# MOD-Y_V02.net
KiCad netlist of a schematic drawn in EAGLE
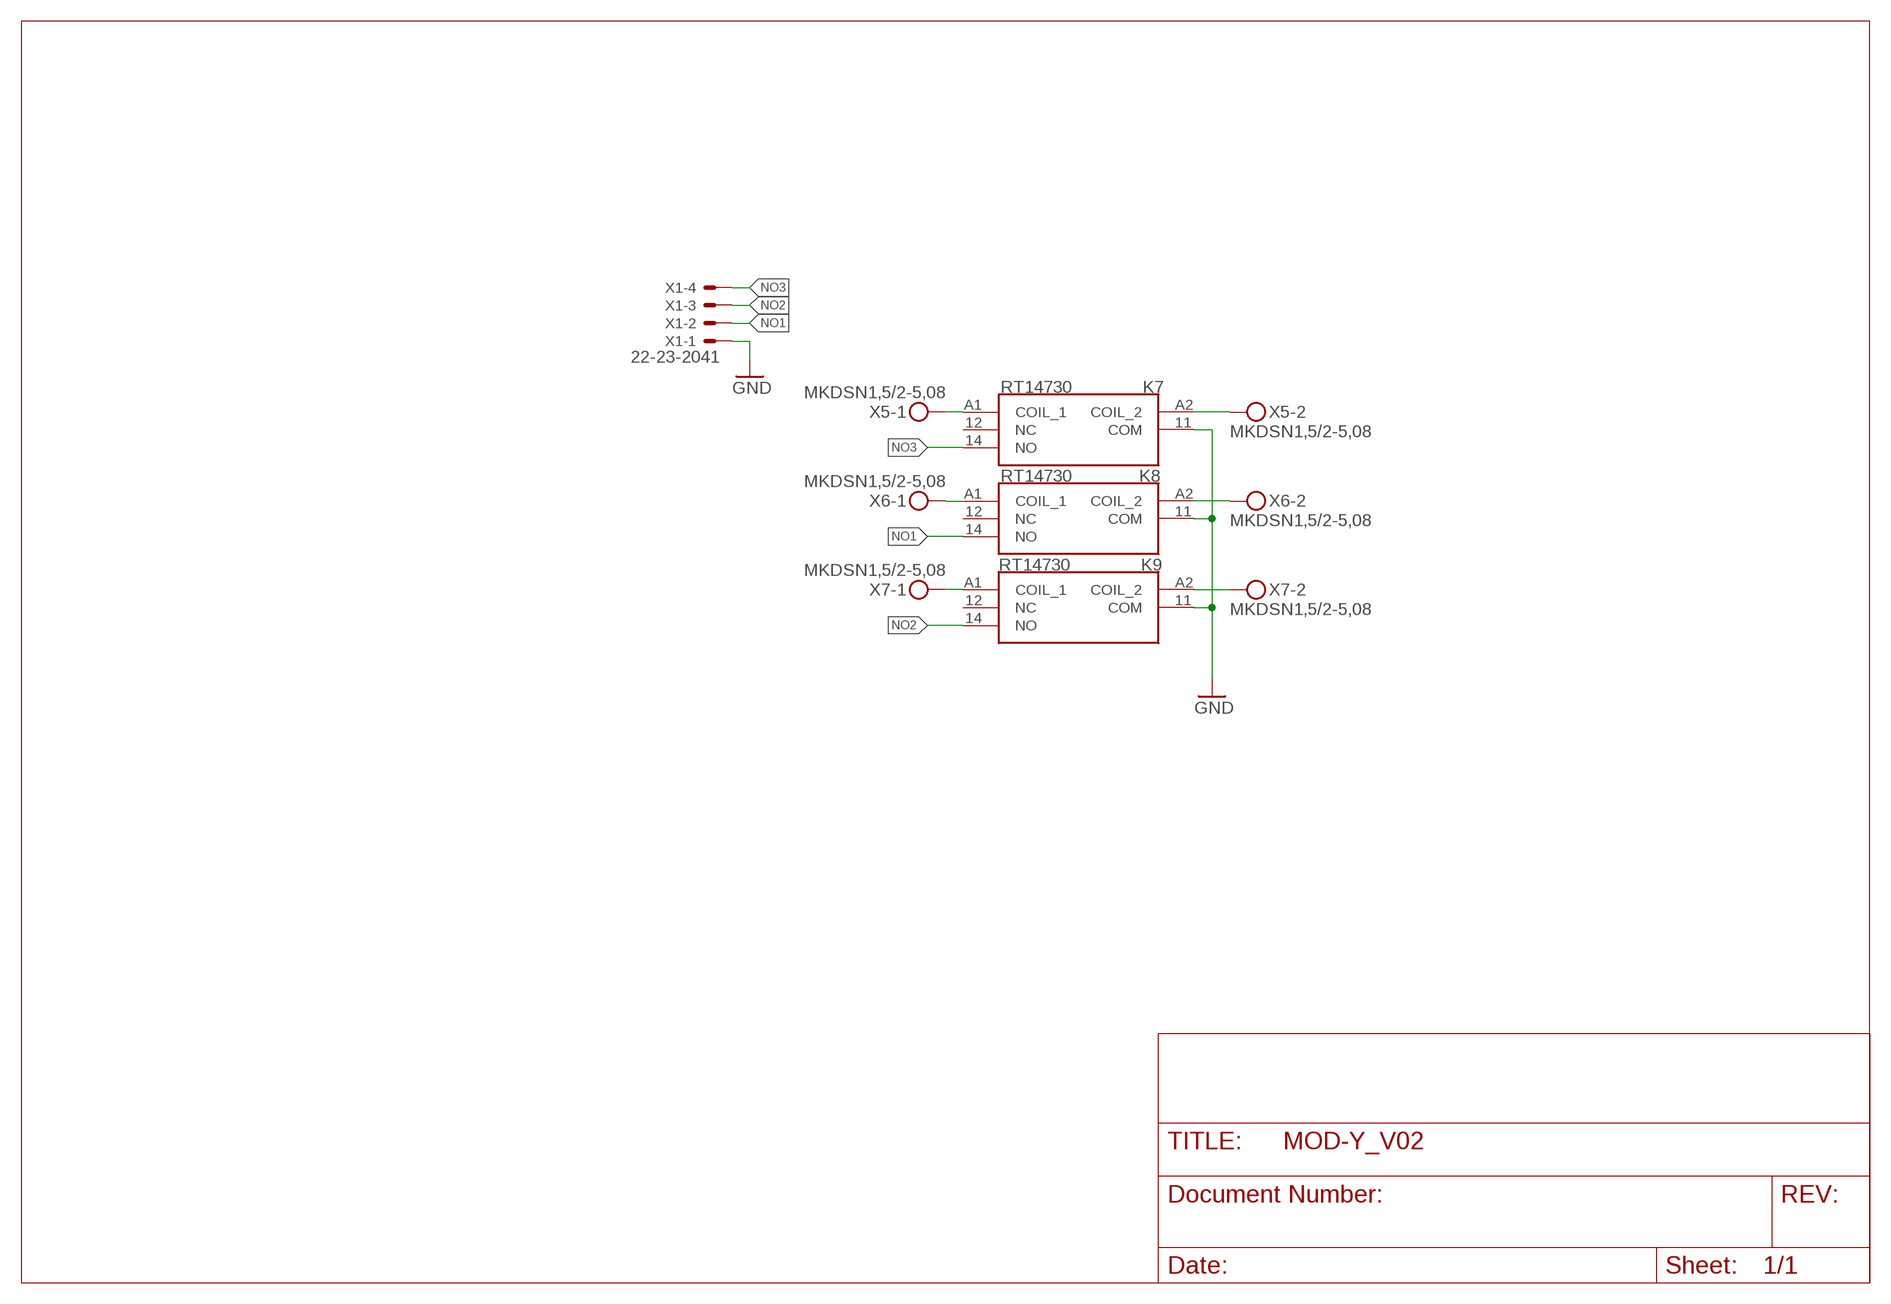
[diagram p0: schematic, sheet 1]

(export (version "E")
  (design (tool "Eeschema 10.0.6"))
  (components
    (comp (ref "K7")
      (value "RT14730")
      (footprint "eagle-import:RT14730")
      (fields (field (name "MANUFACTURER_PART_NUMBER") "rt14730"))
      (libsource (lib "eagle-import") (part "RT14730"))
    )
    (comp (ref "K8")
      (value "RT14730")
      (footprint "eagle-import:RT14730")
      (fields (field (name "MANUFACTURER_PART_NUMBER") "rt14730"))
      (libsource (lib "eagle-import") (part "RT14730"))
    )
    (comp (ref "K9")
      (value "RT14730")
      (footprint "eagle-import:RT14730")
      (fields (field (name "MANUFACTURER_PART_NUMBER") "rt14730"))
      (libsource (lib "eagle-import") (part "RT14730"))
    )
    (comp (ref "X1")
      (value "22-23-2041")
      (footprint "eagle-import:22-23-2041")
      (fields (field (name "MF") "MOLEX"))
      (libsource (lib "eagle-import") (part "22-23-2041"))
    )
    (comp (ref "X5")
      (value "MKDSN1,5/2-5,08")
      (footprint "eagle-import:MKDSN1,5_2-5,08")
      (libsource (lib "eagle-import") (part "MKDSN1,5/2-5,08"))
    )
    (comp (ref "X6")
      (value "MKDSN1,5/2-5,08")
      (footprint "eagle-import:MKDSN1,5_2-5,08")
      (libsource (lib "eagle-import") (part "MKDSN1,5/2-5,08"))
    )
    (comp (ref "X7")
      (value "MKDSN1,5/2-5,08")
      (footprint "eagle-import:MKDSN1,5_2-5,08")
      (libsource (lib "eagle-import") (part "MKDSN1,5/2-5,08"))
    )
  )
  (nets
    (net (code "1") (name "GND") (class "Default")
      (node (ref "K7") (pin "11") (pinfunction "COM_11") (pintype "bidirectional"))
      (node (ref "K8") (pin "11") (pinfunction "COM_11") (pintype "bidirectional"))
      (node (ref "K9") (pin "11") (pinfunction "COM_11") (pintype "bidirectional"))
      (node (ref "X1") (pin "1") (pinfunction "S_1") (pintype "passive"))
    )
    (net (code "2") (name "NO1") (class "Default")
      (node (ref "K8") (pin "14") (pinfunction "NO_14") (pintype "bidirectional"))
      (node (ref "X1") (pin "2") (pinfunction "S_2") (pintype "passive"))
    )
    (net (code "3") (name "NO2") (class "Default")
      (node (ref "K9") (pin "14") (pinfunction "NO_14") (pintype "bidirectional"))
      (node (ref "X1") (pin "3") (pinfunction "S_3") (pintype "passive"))
    )
    (net (code "4") (name "NO3") (class "Default")
      (node (ref "K7") (pin "14") (pinfunction "NO_14") (pintype "bidirectional"))
      (node (ref "X1") (pin "4") (pinfunction "S_4") (pintype "passive"))
    )
    (net (code "5") (name "Net-(K7-COIL_1)") (class "Default")
      (node (ref "K7") (pin "A1") (pinfunction "COIL_1_A1") (pintype "bidirectional"))
      (node (ref "X5") (pin "1") (pinfunction "KL_1") (pintype "passive"))
    )
    (net (code "6") (name "Net-(K7-COIL_2)") (class "Default")
      (node (ref "K7") (pin "A2") (pinfunction "COIL_2_A2") (pintype "bidirectional"))
      (node (ref "X5") (pin "2") (pinfunction "KL_2") (pintype "passive"))
    )
    (net (code "7") (name "Net-(K8-COIL_1)") (class "Default")
      (node (ref "K8") (pin "A1") (pinfunction "COIL_1_A1") (pintype "bidirectional"))
      (node (ref "X6") (pin "1") (pinfunction "KL_1") (pintype "passive"))
    )
    (net (code "8") (name "Net-(K8-COIL_2)") (class "Default")
      (node (ref "K8") (pin "A2") (pinfunction "COIL_2_A2") (pintype "bidirectional"))
      (node (ref "X6") (pin "2") (pinfunction "KL_2") (pintype "passive"))
    )
    (net (code "9") (name "Net-(K9-COIL_1)") (class "Default")
      (node (ref "K9") (pin "A1") (pinfunction "COIL_1_A1") (pintype "bidirectional"))
      (node (ref "X7") (pin "1") (pinfunction "KL_1") (pintype "passive"))
    )
    (net (code "10") (name "Net-(K9-COIL_2)") (class "Default")
      (node (ref "K9") (pin "A2") (pinfunction "COIL_2_A2") (pintype "bidirectional"))
      (node (ref "X7") (pin "2") (pinfunction "KL_2") (pintype "passive"))
    )
    (net (code "11") (name "unconnected-(K7-NC-Pad12)") (class "Default")
      (node (ref "K7") (pin "12") (pinfunction "NC_12") (pintype "no_connect"))
    )
    (net (code "12") (name "unconnected-(K8-NC-Pad12)") (class "Default")
      (node (ref "K8") (pin "12") (pinfunction "NC_12") (pintype "no_connect"))
    )
    (net (code "13") (name "unconnected-(K9-NC-Pad12)") (class "Default")
      (node (ref "K9") (pin "12") (pinfunction "NC_12") (pintype "no_connect"))
    )
  )
)
